# dual_CAN_conn.net
KiCad netlist of a schematic drawn in Altium Designer
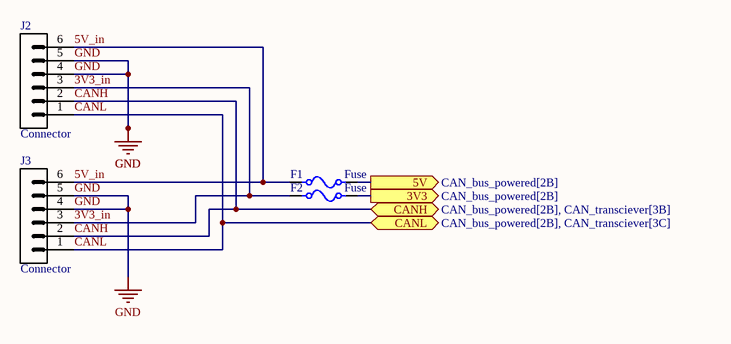
[diagram p0: dual_CAN_conn.SchDoc]

(export (version "E")
  (design (tool "Eeschema 10.0.6"))
  (components
    (comp (ref "F1") (value "Fuse") (libsource (lib "drfc_schlib") (part "Fuse")))
    (comp (ref "F2") (value "Fuse") (libsource (lib "drfc_schlib") (part "Fuse")))
    (comp (ref "J2")
      (value "Connector")
      (description "6 Pin 1 Row Connector")
      (libsource (lib "drfc_schlib") (part "Connector 6-Pin 1 Row"))
    )
    (comp (ref "J3")
      (value "Connector")
      (description "6 Pin 1 Row Connector")
      (libsource (lib "drfc_schlib") (part "Connector 6-Pin 1 Row"))
    )
  )
  (nets
    (net (code "1") (name "/3V3") (class "Default")
      (node (ref "F2") (pin "2") (pinfunction "2_2") (pintype "passive"))
    )
    (net (code "2") (name "/3V3_in") (class "Default")
      (node (ref "F2") (pin "1") (pinfunction "1_1") (pintype "passive"))
      (node (ref "J2") (pin "3") (pinfunction "3_3") (pintype "passive"))
      (node (ref "J3") (pin "3") (pinfunction "3_3") (pintype "passive"))
    )
    (net (code "3") (name "/5V") (class "Default")
      (node (ref "F1") (pin "2") (pinfunction "2_2") (pintype "passive"))
    )
    (net (code "4") (name "/5V_in") (class "Default")
      (node (ref "F1") (pin "1") (pinfunction "1_1") (pintype "passive"))
      (node (ref "J2") (pin "6") (pinfunction "6_6") (pintype "passive"))
      (node (ref "J3") (pin "6") (pinfunction "6_6") (pintype "passive"))
    )
    (net (code "5") (name "/CANH") (class "Default")
      (node (ref "J2") (pin "2") (pinfunction "2_2") (pintype "passive"))
      (node (ref "J3") (pin "2") (pinfunction "2_2") (pintype "passive"))
    )
    (net (code "6") (name "/CANL") (class "Default")
      (node (ref "J2") (pin "1") (pinfunction "1_1") (pintype "passive"))
      (node (ref "J3") (pin "1") (pinfunction "1_1") (pintype "passive"))
    )
    (net (code "7") (name "GND") (class "Default")
      (node (ref "J2") (pin "4") (pinfunction "4_4") (pintype "passive"))
      (node (ref "J2") (pin "5") (pinfunction "5_5") (pintype "passive"))
      (node (ref "J3") (pin "4") (pinfunction "4_4") (pintype "passive"))
      (node (ref "J3") (pin "5") (pinfunction "5_5") (pintype "passive"))
    )
  )
)
